# anemometer-r1.net
KiCad netlist of a schematic drawn in EAGLE
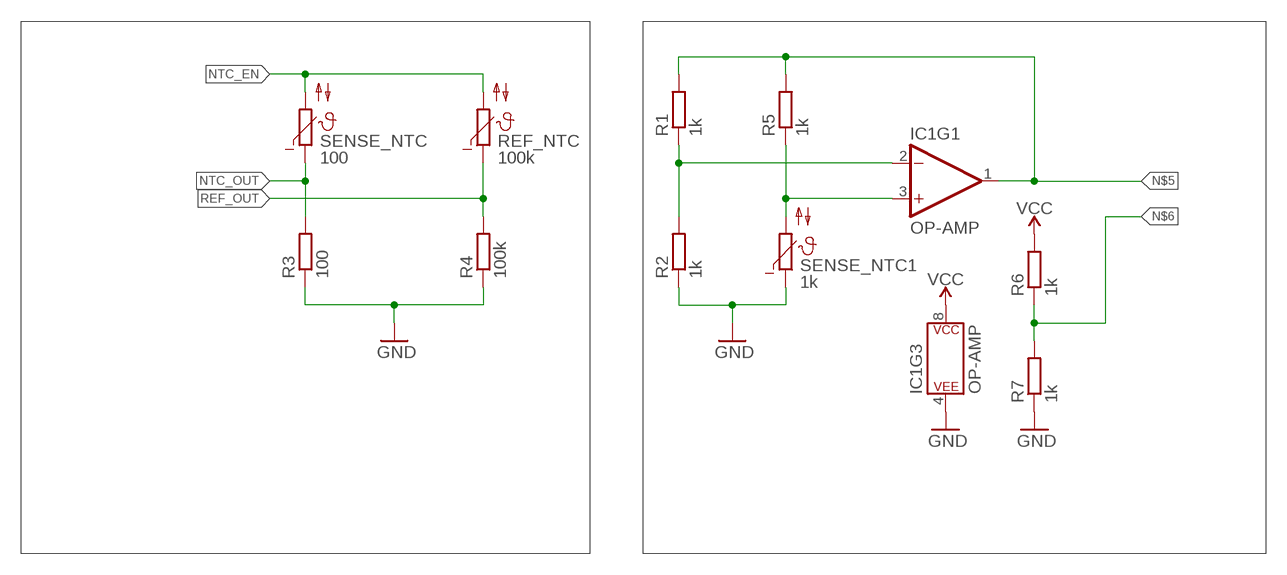
[diagram p0: schematic, sheet 1]

(export (version "E")
  (design (tool "Eeschema 10.0.6"))
  (components
    (comp (ref "IC1")
      (value "OP-AMP")
      (footprint "eagle-import:SO08")
      (libsource (lib "eagle-import") (part "OPAMP-DUALU"))
    )
    (comp (ref "R1")
      (value "1k")
      (footprint "eagle-import:R0603")
      (libsource (lib "eagle-import") (part "R-EU_R0603"))
    )
    (comp (ref "R2")
      (value "1k")
      (footprint "eagle-import:R0603")
      (libsource (lib "eagle-import") (part "R-EU_R0603"))
    )
    (comp (ref "R3")
      (value "100")
      (footprint "eagle-import:R0603")
      (libsource (lib "eagle-import") (part "R-EU_R0603"))
    )
    (comp (ref "R4")
      (value "100k")
      (footprint "eagle-import:R0603")
      (libsource (lib "eagle-import") (part "R-EU_R0603"))
    )
    (comp (ref "R5")
      (value "1k")
      (footprint "eagle-import:R0603")
      (libsource (lib "eagle-import") (part "R-EU_R0603"))
    )
    (comp (ref "R6")
      (value "1k")
      (footprint "eagle-import:R0603")
      (libsource (lib "eagle-import") (part "R-EU_R0603"))
    )
    (comp (ref "R7")
      (value "1k")
      (footprint "eagle-import:R0603")
      (libsource (lib "eagle-import") (part "R-EU_R0603"))
    )
    (comp (ref "REF_NTC")
      (value "100k")
      (footprint "eagle-import:P642")
      (libsource (lib "eagle-import") (part "NTC642-6"))
    )
    (comp (ref "SENSE_NTC")
      (value "100")
      (footprint "eagle-import:P642")
      (libsource (lib "eagle-import") (part "NTC642-6"))
    )
    (comp (ref "SENSE_NTC1")
      (value "1k")
      (footprint "eagle-import:P642")
      (libsource (lib "eagle-import") (part "NTC642-6"))
    )
  )
  (nets
    (net (code "1") (name "GND") (class "Default")
      (node (ref "IC1") (pin "4") (pinfunction "P$V-_4") (pintype "bidirectional"))
      (node (ref "R2") (pin "1") (pinfunction "1_1") (pintype "passive"))
      (node (ref "R3") (pin "1") (pinfunction "1_1") (pintype "passive"))
      (node (ref "R4") (pin "1") (pinfunction "1_1") (pintype "passive"))
      (node (ref "R7") (pin "1") (pinfunction "1_1") (pintype "passive"))
      (node (ref "SENSE_NTC1") (pin "1") (pinfunction "1_1") (pintype "passive"))
    )
    (net (code "2") (name "N$5") (class "Default")
      (node (ref "IC1") (pin "1") (pinfunction "OUT_1") (pintype "output"))
      (node (ref "R1") (pin "2") (pinfunction "2_2") (pintype "passive"))
      (node (ref "R5") (pin "2") (pinfunction "2_2") (pintype "passive"))
    )
    (net (code "3") (name "N$6") (class "Default")
      (node (ref "R6") (pin "1") (pinfunction "1_1") (pintype "passive"))
      (node (ref "R7") (pin "2") (pinfunction "2_2") (pintype "passive"))
    )
    (net (code "4") (name "NTC_EN") (class "Default")
      (node (ref "REF_NTC") (pin "2") (pinfunction "2_2") (pintype "passive"))
      (node (ref "SENSE_NTC") (pin "2") (pinfunction "2_2") (pintype "passive"))
    )
    (net (code "5") (name "NTC_OUT") (class "Default")
      (node (ref "R3") (pin "2") (pinfunction "2_2") (pintype "passive"))
      (node (ref "SENSE_NTC") (pin "1") (pinfunction "1_1") (pintype "passive"))
    )
    (net (code "6") (name "Net-(IC1A-+IN)") (class "Default")
      (node (ref "IC1") (pin "3") (pinfunction "+IN_3") (pintype "input"))
      (node (ref "R5") (pin "1") (pinfunction "1_1") (pintype "passive"))
      (node (ref "SENSE_NTC1") (pin "2") (pinfunction "2_2") (pintype "passive"))
    )
    (net (code "7") (name "Net-(IC1A--IN)") (class "Default")
      (node (ref "IC1") (pin "2") (pinfunction "-IN_2") (pintype "input"))
      (node (ref "R1") (pin "1") (pinfunction "1_1") (pintype "passive"))
      (node (ref "R2") (pin "2") (pinfunction "2_2") (pintype "passive"))
    )
    (net (code "8") (name "REF_OUT") (class "Default")
      (node (ref "R4") (pin "2") (pinfunction "2_2") (pintype "passive"))
      (node (ref "REF_NTC") (pin "1") (pinfunction "1_1") (pintype "passive"))
    )
    (net (code "9") (name "VCC") (class "Default")
      (node (ref "IC1") (pin "8") (pinfunction "P$V+_8") (pintype "bidirectional"))
      (node (ref "R6") (pin "2") (pinfunction "2_2") (pintype "passive"))
    )
  )
)
